# protoboard.net
KiCad netlist of a schematic drawn in Altium Designer
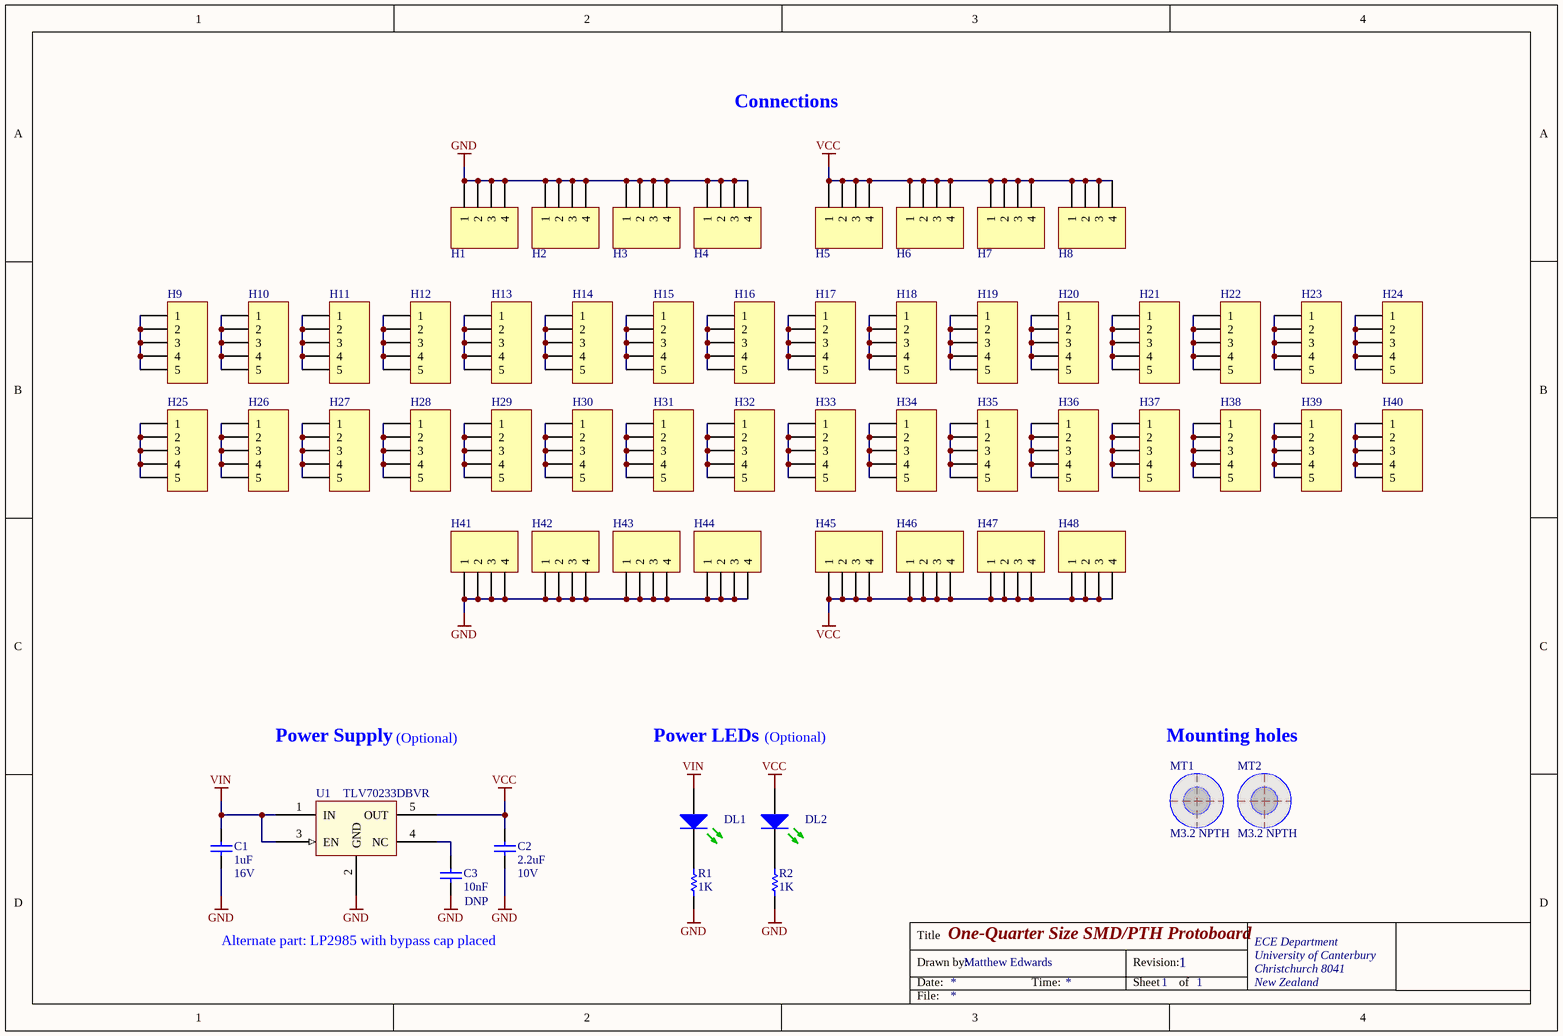
[diagram p0: protoboard.SchDoc]

(export (version "E")
  (design (tool "Eeschema 10.0.6"))
  (components
    (comp (ref "C1")
      (value "1uF")
      (footprint "CAPC1608L")
      (description "CAP CER 1uF Y5V -20% +80% 16V 0603")
      (fields (field (name "MAX VOLTAGE") "16V"))
      (libsource (lib "CAP_MLCC_E12") (part "CC_1uF_0603"))
    )
    (comp (ref "C2")
      (value "2.2uF")
      (footprint "CAPC1608L")
      (description "CAP CER 2.2uF X5R +-20% 10V 0603")
      (fields (field (name "MAX VOLTAGE") "10V"))
      (libsource (lib "CAP_MLCC_E12") (part "CC_2.2uF_0603"))
    )
    (comp (ref "C3")
      (value "DNP")
      (footprint "CAPC1608L")
      (description "CAP CER 10nF X7R +-10% 50V 0603")
      (fields (field (name "ALTIUM_VALUE") "10nF"))
      (libsource (lib "CAP_MLCC_E12") (part "CC_10nF_0603"))
    )
    (comp (ref "DL1")
      (value "Dark Green")
      (footprint "WL-SMCW0603")
      (description "LED Dk Green 430mcd 0603 SMD")
      (fields
        (field (name "MANUFACTURER") "WURTH ELEKTRONIK")
        (field (name "MANUFACTURER PART NUMBER") "150060GS75000")
      )
      (libsource (lib "SEMI_DISCRETE") (part "DL_150060GS75000"))
    )
    (comp (ref "DL2")
      (value "Dark Green")
      (footprint "WL-SMCW0603")
      (description "LED Dk Green 430mcd 0603 SMD")
      (fields
        (field (name "MANUFACTURER") "WURTH ELEKTRONIK")
        (field (name "MANUFACTURER PART NUMBER") "150060GS75000")
      )
      (libsource (lib "SEMI_DISCRETE") (part "DL_150060GS75000"))
    )
    (comp (ref "H1")
      (value "CONN_04")
      (footprint "1X04 hex")
      (description "CONN HEADER 4POS 2.54mm VERT_Thru Hole")
      (libsource (lib "protoboard") (part "CONN_04"))
    )
    (comp (ref "H2")
      (value "CONN_04")
      (footprint "1X04 hex")
      (description "CONN HEADER 4POS 2.54mm VERT_Thru Hole")
      (libsource (lib "protoboard") (part "CONN_04"))
    )
    (comp (ref "H3")
      (value "CONN_04")
      (footprint "1X04 hex")
      (description "CONN HEADER 4POS 2.54mm VERT_Thru Hole")
      (libsource (lib "protoboard") (part "CONN_04"))
    )
    (comp (ref "H4")
      (value "CONN_04")
      (footprint "1X04 hex")
      (description "CONN HEADER 4POS 2.54mm VERT_Thru Hole")
      (libsource (lib "protoboard") (part "CONN_04"))
    )
    (comp (ref "H5")
      (value "CONN_04")
      (footprint "1X04 hex")
      (description "CONN HEADER 4POS 2.54mm VERT_Thru Hole")
      (libsource (lib "protoboard") (part "CONN_04"))
    )
    (comp (ref "H6")
      (value "CONN_04")
      (footprint "1X04 hex")
      (description "CONN HEADER 4POS 2.54mm VERT_Thru Hole")
      (libsource (lib "protoboard") (part "CONN_04"))
    )
    (comp (ref "H7")
      (value "CONN_04")
      (footprint "1X04 hex")
      (description "CONN HEADER 4POS 2.54mm VERT_Thru Hole")
      (libsource (lib "protoboard") (part "CONN_04"))
    )
    (comp (ref "H8")
      (value "CONN_04")
      (footprint "1X04 hex")
      (description "CONN HEADER 4POS 2.54mm VERT_Thru Hole")
      (libsource (lib "protoboard") (part "CONN_04"))
    )
    (comp (ref "H9")
      (value "CONN_05")
      (footprint "1X05 square")
      (description "CONN HEADER 5POS 2.54mm VERT_Thru Hole")
      (libsource (lib "protoboard") (part "CONN_05"))
    )
    (comp (ref "H10")
      (value "CONN_05")
      (footprint "1X05 square")
      (description "CONN HEADER 5POS 2.54mm VERT_Thru Hole")
      (libsource (lib "protoboard") (part "CONN_05"))
    )
    (comp (ref "H11")
      (value "CONN_05")
      (footprint "1X05 square")
      (description "CONN HEADER 5POS 2.54mm VERT_Thru Hole")
      (libsource (lib "protoboard") (part "CONN_05"))
    )
    (comp (ref "H12")
      (value "CONN_05")
      (footprint "1X05 square")
      (description "CONN HEADER 5POS 2.54mm VERT_Thru Hole")
      (libsource (lib "protoboard") (part "CONN_05"))
    )
    (comp (ref "H13")
      (value "CONN_05")
      (footprint "1X05 square")
      (description "CONN HEADER 5POS 2.54mm VERT_Thru Hole")
      (libsource (lib "protoboard") (part "CONN_05"))
    )
    (comp (ref "H14")
      (value "CONN_05")
      (footprint "1X05 square")
      (description "CONN HEADER 5POS 2.54mm VERT_Thru Hole")
      (libsource (lib "protoboard") (part "CONN_05"))
    )
    (comp (ref "H15")
      (value "CONN_05")
      (footprint "1X05 square")
      (description "CONN HEADER 5POS 2.54mm VERT_Thru Hole")
      (libsource (lib "protoboard") (part "CONN_05"))
    )
    (comp (ref "H16")
      (value "CONN_05")
      (footprint "1X05 square")
      (description "CONN HEADER 5POS 2.54mm VERT_Thru Hole")
      (libsource (lib "protoboard") (part "CONN_05"))
    )
    (comp (ref "H17")
      (value "CONN_05")
      (footprint "1X05 square")
      (description "CONN HEADER 5POS 2.54mm VERT_Thru Hole")
      (libsource (lib "protoboard") (part "CONN_05"))
    )
    (comp (ref "H18")
      (value "CONN_05")
      (footprint "1X05 square")
      (description "CONN HEADER 5POS 2.54mm VERT_Thru Hole")
      (libsource (lib "protoboard") (part "CONN_05"))
    )
    (comp (ref "H19")
      (value "CONN_05")
      (footprint "1X05 square")
      (description "CONN HEADER 5POS 2.54mm VERT_Thru Hole")
      (libsource (lib "protoboard") (part "CONN_05"))
    )
    (comp (ref "H20")
      (value "CONN_05")
      (footprint "1X05 square")
      (description "CONN HEADER 5POS 2.54mm VERT_Thru Hole")
      (libsource (lib "protoboard") (part "CONN_05"))
    )
    (comp (ref "H21")
      (value "CONN_05")
      (footprint "1X05 square")
      (description "CONN HEADER 5POS 2.54mm VERT_Thru Hole")
      (libsource (lib "protoboard") (part "CONN_05"))
    )
    (comp (ref "H22")
      (value "CONN_05")
      (footprint "1X05 square")
      (description "CONN HEADER 5POS 2.54mm VERT_Thru Hole")
      (libsource (lib "protoboard") (part "CONN_05"))
    )
    (comp (ref "H23")
      (value "CONN_05")
      (footprint "1X05 square")
      (description "CONN HEADER 5POS 2.54mm VERT_Thru Hole")
      (libsource (lib "protoboard") (part "CONN_05"))
    )
    (comp (ref "H24")
      (value "CONN_05")
      (footprint "1X05 square")
      (description "CONN HEADER 5POS 2.54mm VERT_Thru Hole")
      (libsource (lib "protoboard") (part "CONN_05"))
    )
    (comp (ref "H25")
      (value "CONN_05")
      (footprint "1X05 square")
      (description "CONN HEADER 5POS 2.54mm VERT_Thru Hole")
      (libsource (lib "protoboard") (part "CONN_05"))
    )
    (comp (ref "H26")
      (value "CONN_05")
      (footprint "1X05 square")
      (description "CONN HEADER 5POS 2.54mm VERT_Thru Hole")
      (libsource (lib "protoboard") (part "CONN_05"))
    )
    (comp (ref "H27")
      (value "CONN_05")
      (footprint "1X05 square")
      (description "CONN HEADER 5POS 2.54mm VERT_Thru Hole")
      (libsource (lib "protoboard") (part "CONN_05"))
    )
    (comp (ref "H28")
      (value "CONN_05")
      (footprint "1X05 square")
      (description "CONN HEADER 5POS 2.54mm VERT_Thru Hole")
      (libsource (lib "protoboard") (part "CONN_05"))
    )
    (comp (ref "H29")
      (value "CONN_05")
      (footprint "1X05 square")
      (description "CONN HEADER 5POS 2.54mm VERT_Thru Hole")
      (libsource (lib "protoboard") (part "CONN_05"))
    )
    (comp (ref "H30")
      (value "CONN_05")
      (footprint "1X05 square")
      (description "CONN HEADER 5POS 2.54mm VERT_Thru Hole")
      (libsource (lib "protoboard") (part "CONN_05"))
    )
    (comp (ref "H31")
      (value "CONN_05")
      (footprint "1X05 square")
      (description "CONN HEADER 5POS 2.54mm VERT_Thru Hole")
      (libsource (lib "protoboard") (part "CONN_05"))
    )
    (comp (ref "H32")
      (value "CONN_05")
      (footprint "1X05 square")
      (description "CONN HEADER 5POS 2.54mm VERT_Thru Hole")
      (libsource (lib "protoboard") (part "CONN_05"))
    )
    (comp (ref "H33")
      (value "CONN_05")
      (footprint "1X05 square")
      (description "CONN HEADER 5POS 2.54mm VERT_Thru Hole")
      (libsource (lib "protoboard") (part "CONN_05"))
    )
    (comp (ref "H34")
      (value "CONN_05")
      (footprint "1X05 square")
      (description "CONN HEADER 5POS 2.54mm VERT_Thru Hole")
      (libsource (lib "protoboard") (part "CONN_05"))
    )
    (comp (ref "H35")
      (value "CONN_05")
      (footprint "1X05 square")
      (description "CONN HEADER 5POS 2.54mm VERT_Thru Hole")
      (libsource (lib "protoboard") (part "CONN_05"))
    )
    (comp (ref "H36")
      (value "CONN_05")
      (footprint "1X05 square")
      (description "CONN HEADER 5POS 2.54mm VERT_Thru Hole")
      (libsource (lib "protoboard") (part "CONN_05"))
    )
    (comp (ref "H37")
      (value "CONN_05")
      (footprint "1X05 square")
      (description "CONN HEADER 5POS 2.54mm VERT_Thru Hole")
      (libsource (lib "protoboard") (part "CONN_05"))
    )
    (comp (ref "H38")
      (value "CONN_05")
      (footprint "1X05 square")
      (description "CONN HEADER 5POS 2.54mm VERT_Thru Hole")
      (libsource (lib "protoboard") (part "CONN_05"))
    )
    (comp (ref "H39")
      (value "CONN_05")
      (footprint "1X05 square")
      (description "CONN HEADER 5POS 2.54mm VERT_Thru Hole")
      (libsource (lib "protoboard") (part "CONN_05"))
    )
    (comp (ref "H40")
      (value "CONN_05")
      (footprint "1X05 square")
      (description "CONN HEADER 5POS 2.54mm VERT_Thru Hole")
      (libsource (lib "protoboard") (part "CONN_05"))
    )
    (comp (ref "H41")
      (value "CONN_04")
      (footprint "1X04 hex")
      (description "CONN HEADER 4POS 2.54mm VERT_Thru Hole")
      (libsource (lib "") (part "CONN_04_1"))
    )
    (comp (ref "H42")
      (value "CONN_04")
      (footprint "1X04 hex")
      (description "CONN HEADER 4POS 2.54mm VERT_Thru Hole")
      (libsource (lib "") (part "CONN_04_1"))
    )
    (comp (ref "H43")
      (value "CONN_04")
      (footprint "1X04 hex")
      (description "CONN HEADER 4POS 2.54mm VERT_Thru Hole")
      (libsource (lib "") (part "CONN_04_1"))
    )
    (comp (ref "H44")
      (value "CONN_04")
      (footprint "1X04 hex")
      (description "CONN HEADER 4POS 2.54mm VERT_Thru Hole")
      (libsource (lib "") (part "CONN_04_1"))
    )
    (comp (ref "H45")
      (value "CONN_04")
      (footprint "1X04 hex")
      (description "CONN HEADER 4POS 2.54mm VERT_Thru Hole")
      (libsource (lib "") (part "CONN_04_1"))
    )
    (comp (ref "H46")
      (value "CONN_04")
      (footprint "1X04 hex")
      (description "CONN HEADER 4POS 2.54mm VERT_Thru Hole")
      (libsource (lib "") (part "CONN_04_1"))
    )
    (comp (ref "H47")
      (value "CONN_04")
      (footprint "1X04 hex")
      (description "CONN HEADER 4POS 2.54mm VERT_Thru Hole")
      (libsource (lib "") (part "CONN_04_1"))
    )
    (comp (ref "H48")
      (value "CONN_04")
      (footprint "1X04 hex")
      (description "CONN HEADER 4POS 2.54mm VERT_Thru Hole")
      (libsource (lib "") (part "CONN_04_1"))
    )
    (comp (ref "MT1")
      (value "M3.2 NPTH")
      (footprint "MNT-HOLE_3.2mm_NPTH")
      (description "Fixing M3.2 Mount Hole NPTH")
      (fields (field (name "MANUFACTURER") "Hi-Q"))
      (libsource (lib "MISC_Passive") (part "MC_M3.2_HOLE"))
    )
    (comp (ref "MT2")
      (value "M3.2 NPTH")
      (footprint "MNT-HOLE_3.2mm_NPTH")
      (description "Fixing M3.2 Mount Hole NPTH")
      (fields (field (name "MANUFACTURER") "Hi-Q"))
      (libsource (lib "MISC_Passive") (part "MC_M3.2_HOLE"))
    )
    (comp (ref "R1")
      (value "1K")
      (footprint "RESC1608L")
      (description "RES 1.0K OHM 1/10W 5% 0603 SMD")
      (libsource (lib "RES_0603_0.1W_E24") (part "RS_1K"))
    )
    (comp (ref "R2")
      (value "1K")
      (footprint "RESC1608L")
      (description "RES 1.0K OHM 1/10W 5% 0603 SMD")
      (libsource (lib "RES_0603_0.1W_E24") (part "RS_1K"))
    )
    (comp (ref "U1")
      (value "TLV70233DBVR")
      (footprint "SOT95P280X145-5N")
      (description "IC REG LDO 3.3V 0.3A SOT23-5")
      (fields
        (field (name "MANUFACTURER") "Texas Instruments")
        (field (name "MANUFACTURER PART NUMBER") "TLV70233DBVR")
      )
      (libsource (lib "SEMI_DISCRETE") (part "SV_TLV70233DBVR"))
    )
  )
  (nets
    (net (code "1") (name "GND") (class "Default")
      (node (ref "C1") (pin "1") (pinfunction "1_1") (pintype "passive"))
      (node (ref "C2") (pin "1") (pinfunction "1_1") (pintype "passive"))
      (node (ref "C3") (pin "2") (pinfunction "2_2") (pintype "passive"))
      (node (ref "H1") (pin "1") (pinfunction "1_1") (pintype "passive"))
      (node (ref "H1") (pin "2") (pinfunction "2_2") (pintype "passive"))
      (node (ref "H1") (pin "3") (pinfunction "3_3") (pintype "passive"))
      (node (ref "H1") (pin "4") (pinfunction "4_4") (pintype "passive"))
      (node (ref "H2") (pin "1") (pinfunction "1_1") (pintype "passive"))
      (node (ref "H2") (pin "2") (pinfunction "2_2") (pintype "passive"))
      (node (ref "H2") (pin "3") (pinfunction "3_3") (pintype "passive"))
      (node (ref "H2") (pin "4") (pinfunction "4_4") (pintype "passive"))
      (node (ref "H3") (pin "1") (pinfunction "1_1") (pintype "passive"))
      (node (ref "H3") (pin "2") (pinfunction "2_2") (pintype "passive"))
      (node (ref "H3") (pin "3") (pinfunction "3_3") (pintype "passive"))
      (node (ref "H3") (pin "4") (pinfunction "4_4") (pintype "passive"))
      (node (ref "H4") (pin "1") (pinfunction "1_1") (pintype "passive"))
      (node (ref "H4") (pin "2") (pinfunction "2_2") (pintype "passive"))
      (node (ref "H4") (pin "3") (pinfunction "3_3") (pintype "passive"))
      (node (ref "H4") (pin "4") (pinfunction "4_4") (pintype "passive"))
      (node (ref "H41") (pin "1") (pinfunction "1_1") (pintype "passive"))
      (node (ref "H41") (pin "2") (pinfunction "2_2") (pintype "passive"))
      (node (ref "H41") (pin "3") (pinfunction "3_3") (pintype "passive"))
      (node (ref "H41") (pin "4") (pinfunction "4_4") (pintype "passive"))
      (node (ref "H42") (pin "1") (pinfunction "1_1") (pintype "passive"))
      (node (ref "H42") (pin "2") (pinfunction "2_2") (pintype "passive"))
      (node (ref "H42") (pin "3") (pinfunction "3_3") (pintype "passive"))
      (node (ref "H42") (pin "4") (pinfunction "4_4") (pintype "passive"))
      (node (ref "H43") (pin "1") (pinfunction "1_1") (pintype "passive"))
      (node (ref "H43") (pin "2") (pinfunction "2_2") (pintype "passive"))
      (node (ref "H43") (pin "3") (pinfunction "3_3") (pintype "passive"))
      (node (ref "H43") (pin "4") (pinfunction "4_4") (pintype "passive"))
      (node (ref "H44") (pin "1") (pinfunction "1_1") (pintype "passive"))
      (node (ref "H44") (pin "2") (pinfunction "2_2") (pintype "passive"))
      (node (ref "H44") (pin "3") (pinfunction "3_3") (pintype "passive"))
      (node (ref "H44") (pin "4") (pinfunction "4_4") (pintype "passive"))
      (node (ref "R1") (pin "1") (pinfunction "1_1") (pintype "passive"))
      (node (ref "R2") (pin "1") (pinfunction "1_1") (pintype "passive"))
      (node (ref "U1") (pin "2") (pinfunction "GND_2") (pintype "power_in"))
    )
    (net (code "2") (name "Net-(DL1-K)") (class "Default")
      (node (ref "DL1") (pin "1") (pinfunction "K_1") (pintype "passive"))
      (node (ref "R1") (pin "2") (pinfunction "2_2") (pintype "passive"))
    )
    (net (code "3") (name "Net-(DL2-K)") (class "Default")
      (node (ref "DL2") (pin "1") (pinfunction "K_1") (pintype "passive"))
      (node (ref "R2") (pin "2") (pinfunction "2_2") (pintype "passive"))
    )
    (net (code "4") (name "Net-(H9-Pad1)") (class "Default")
      (node (ref "H9") (pin "1") (pinfunction "1_1") (pintype "passive"))
      (node (ref "H9") (pin "2") (pinfunction "2_2") (pintype "passive"))
      (node (ref "H9") (pin "3") (pinfunction "3_3") (pintype "passive"))
      (node (ref "H9") (pin "4") (pinfunction "4_4") (pintype "passive"))
      (node (ref "H9") (pin "5") (pinfunction "5_5") (pintype "passive"))
    )
    (net (code "5") (name "Net-(H10-Pad1)") (class "Default")
      (node (ref "H10") (pin "1") (pinfunction "1_1") (pintype "passive"))
      (node (ref "H10") (pin "2") (pinfunction "2_2") (pintype "passive"))
      (node (ref "H10") (pin "3") (pinfunction "3_3") (pintype "passive"))
      (node (ref "H10") (pin "4") (pinfunction "4_4") (pintype "passive"))
      (node (ref "H10") (pin "5") (pinfunction "5_5") (pintype "passive"))
    )
    (net (code "6") (name "Net-(H11-Pad1)") (class "Default")
      (node (ref "H11") (pin "1") (pinfunction "1_1") (pintype "passive"))
      (node (ref "H11") (pin "2") (pinfunction "2_2") (pintype "passive"))
      (node (ref "H11") (pin "3") (pinfunction "3_3") (pintype "passive"))
      (node (ref "H11") (pin "4") (pinfunction "4_4") (pintype "passive"))
      (node (ref "H11") (pin "5") (pinfunction "5_5") (pintype "passive"))
    )
    (net (code "7") (name "Net-(H12-Pad1)") (class "Default")
      (node (ref "H12") (pin "1") (pinfunction "1_1") (pintype "passive"))
      (node (ref "H12") (pin "2") (pinfunction "2_2") (pintype "passive"))
      (node (ref "H12") (pin "3") (pinfunction "3_3") (pintype "passive"))
      (node (ref "H12") (pin "4") (pinfunction "4_4") (pintype "passive"))
      (node (ref "H12") (pin "5") (pinfunction "5_5") (pintype "passive"))
    )
    (net (code "8") (name "Net-(H13-Pad1)") (class "Default")
      (node (ref "H13") (pin "1") (pinfunction "1_1") (pintype "passive"))
      (node (ref "H13") (pin "2") (pinfunction "2_2") (pintype "passive"))
      (node (ref "H13") (pin "3") (pinfunction "3_3") (pintype "passive"))
      (node (ref "H13") (pin "4") (pinfunction "4_4") (pintype "passive"))
      (node (ref "H13") (pin "5") (pinfunction "5_5") (pintype "passive"))
    )
    (net (code "9") (name "Net-(H14-Pad1)") (class "Default")
      (node (ref "H14") (pin "1") (pinfunction "1_1") (pintype "passive"))
      (node (ref "H14") (pin "2") (pinfunction "2_2") (pintype "passive"))
      (node (ref "H14") (pin "3") (pinfunction "3_3") (pintype "passive"))
      (node (ref "H14") (pin "4") (pinfunction "4_4") (pintype "passive"))
      (node (ref "H14") (pin "5") (pinfunction "5_5") (pintype "passive"))
    )
    (net (code "10") (name "Net-(H15-Pad1)") (class "Default")
      (node (ref "H15") (pin "1") (pinfunction "1_1") (pintype "passive"))
      (node (ref "H15") (pin "2") (pinfunction "2_2") (pintype "passive"))
      (node (ref "H15") (pin "3") (pinfunction "3_3") (pintype "passive"))
      (node (ref "H15") (pin "4") (pinfunction "4_4") (pintype "passive"))
      (node (ref "H15") (pin "5") (pinfunction "5_5") (pintype "passive"))
    )
    (net (code "11") (name "Net-(H16-Pad1)") (class "Default")
      (node (ref "H16") (pin "1") (pinfunction "1_1") (pintype "passive"))
      (node (ref "H16") (pin "2") (pinfunction "2_2") (pintype "passive"))
      (node (ref "H16") (pin "3") (pinfunction "3_3") (pintype "passive"))
      (node (ref "H16") (pin "4") (pinfunction "4_4") (pintype "passive"))
      (node (ref "H16") (pin "5") (pinfunction "5_5") (pintype "passive"))
    )
    (net (code "12") (name "Net-(H17-Pad1)") (class "Default")
      (node (ref "H17") (pin "1") (pinfunction "1_1") (pintype "passive"))
      (node (ref "H17") (pin "2") (pinfunction "2_2") (pintype "passive"))
      (node (ref "H17") (pin "3") (pinfunction "3_3") (pintype "passive"))
      (node (ref "H17") (pin "4") (pinfunction "4_4") (pintype "passive"))
      (node (ref "H17") (pin "5") (pinfunction "5_5") (pintype "passive"))
    )
    (net (code "13") (name "Net-(H18-Pad1)") (class "Default")
      (node (ref "H18") (pin "1") (pinfunction "1_1") (pintype "passive"))
      (node (ref "H18") (pin "2") (pinfunction "2_2") (pintype "passive"))
      (node (ref "H18") (pin "3") (pinfunction "3_3") (pintype "passive"))
      (node (ref "H18") (pin "4") (pinfunction "4_4") (pintype "passive"))
      (node (ref "H18") (pin "5") (pinfunction "5_5") (pintype "passive"))
    )
    (net (code "14") (name "Net-(H19-Pad1)") (class "Default")
      (node (ref "H19") (pin "1") (pinfunction "1_1") (pintype "passive"))
      (node (ref "H19") (pin "2") (pinfunction "2_2") (pintype "passive"))
      (node (ref "H19") (pin "3") (pinfunction "3_3") (pintype "passive"))
      (node (ref "H19") (pin "4") (pinfunction "4_4") (pintype "passive"))
      (node (ref "H19") (pin "5") (pinfunction "5_5") (pintype "passive"))
    )
    (net (code "15") (name "Net-(H20-Pad1)") (class "Default")
      (node (ref "H20") (pin "1") (pinfunction "1_1") (pintype "passive"))
      (node (ref "H20") (pin "2") (pinfunction "2_2") (pintype "passive"))
      (node (ref "H20") (pin "3") (pinfunction "3_3") (pintype "passive"))
      (node (ref "H20") (pin "4") (pinfunction "4_4") (pintype "passive"))
      (node (ref "H20") (pin "5") (pinfunction "5_5") (pintype "passive"))
    )
    (net (code "16") (name "Net-(H21-Pad1)") (class "Default")
      (node (ref "H21") (pin "1") (pinfunction "1_1") (pintype "passive"))
      (node (ref "H21") (pin "2") (pinfunction "2_2") (pintype "passive"))
      (node (ref "H21") (pin "3") (pinfunction "3_3") (pintype "passive"))
      (node (ref "H21") (pin "4") (pinfunction "4_4") (pintype "passive"))
      (node (ref "H21") (pin "5") (pinfunction "5_5") (pintype "passive"))
    )
    (net (code "17") (name "Net-(H22-Pad1)") (class "Default")
      (node (ref "H22") (pin "1") (pinfunction "1_1") (pintype "passive"))
      (node (ref "H22") (pin "2") (pinfunction "2_2") (pintype "passive"))
      (node (ref "H22") (pin "3") (pinfunction "3_3") (pintype "passive"))
      (node (ref "H22") (pin "4") (pinfunction "4_4") (pintype "passive"))
      (node (ref "H22") (pin "5") (pinfunction "5_5") (pintype "passive"))
    )
    (net (code "18") (name "Net-(H23-Pad1)") (class "Default")
      (node (ref "H23") (pin "1") (pinfunction "1_1") (pintype "passive"))
      (node (ref "H23") (pin "2") (pinfunction "2_2") (pintype "passive"))
      (node (ref "H23") (pin "3") (pinfunction "3_3") (pintype "passive"))
      (node (ref "H23") (pin "4") (pinfunction "4_4") (pintype "passive"))
      (node (ref "H23") (pin "5") (pinfunction "5_5") (pintype "passive"))
    )
    (net (code "19") (name "Net-(H24-Pad1)") (class "Default")
      (node (ref "H24") (pin "1") (pinfunction "1_1") (pintype "passive"))
      (node (ref "H24") (pin "2") (pinfunction "2_2") (pintype "passive"))
      (node (ref "H24") (pin "3") (pinfunction "3_3") (pintype "passive"))
      (node (ref "H24") (pin "4") (pinfunction "4_4") (pintype "passive"))
      (node (ref "H24") (pin "5") (pinfunction "5_5") (pintype "passive"))
    )
    (net (code "20") (name "Net-(H25-Pad1)") (class "Default")
      (node (ref "H25") (pin "1") (pinfunction "1_1") (pintype "passive"))
      (node (ref "H25") (pin "2") (pinfunction "2_2") (pintype "passive"))
      (node (ref "H25") (pin "3") (pinfunction "3_3") (pintype "passive"))
      (node (ref "H25") (pin "4") (pinfunction "4_4") (pintype "passive"))
      (node (ref "H25") (pin "5") (pinfunction "5_5") (pintype "passive"))
    )
    (net (code "21") (name "Net-(H26-Pad1)") (class "Default")
      (node (ref "H26") (pin "1") (pinfunction "1_1") (pintype "passive"))
      (node (ref "H26") (pin "2") (pinfunction "2_2") (pintype "passive"))
      (node (ref "H26") (pin "3") (pinfunction "3_3") (pintype "passive"))
      (node (ref "H26") (pin "4") (pinfunction "4_4") (pintype "passive"))
      (node (ref "H26") (pin "5") (pinfunction "5_5") (pintype "passive"))
    )
    (net (code "22") (name "Net-(H27-Pad1)") (class "Default")
      (node (ref "H27") (pin "1") (pinfunction "1_1") (pintype "passive"))
      (node (ref "H27") (pin "2") (pinfunction "2_2") (pintype "passive"))
      (node (ref "H27") (pin "3") (pinfunction "3_3") (pintype "passive"))
      (node (ref "H27") (pin "4") (pinfunction "4_4") (pintype "passive"))
      (node (ref "H27") (pin "5") (pinfunction "5_5") (pintype "passive"))
    )
    (net (code "23") (name "Net-(H28-Pad1)") (class "Default")
      (node (ref "H28") (pin "1") (pinfunction "1_1") (pintype "passive"))
      (node (ref "H28") (pin "2") (pinfunction "2_2") (pintype "passive"))
      (node (ref "H28") (pin "3") (pinfunction "3_3") (pintype "passive"))
      (node (ref "H28") (pin "4") (pinfunction "4_4") (pintype "passive"))
      (node (ref "H28") (pin "5") (pinfunction "5_5") (pintype "passive"))
    )
    (net (code "24") (name "Net-(H29-Pad1)") (class "Default")
      (node (ref "H29") (pin "1") (pinfunction "1_1") (pintype "passive"))
      (node (ref "H29") (pin "2") (pinfunction "2_2") (pintype "passive"))
      (node (ref "H29") (pin "3") (pinfunction "3_3") (pintype "passive"))
      (node (ref "H29") (pin "4") (pinfunction "4_4") (pintype "passive"))
      (node (ref "H29") (pin "5") (pinfunction "5_5") (pintype "passive"))
    )
    (net (code "25") (name "Net-(H30-Pad1)") (class "Default")
      (node (ref "H30") (pin "1") (pinfunction "1_1") (pintype "passive"))
      (node (ref "H30") (pin "2") (pinfunction "2_2") (pintype "passive"))
      (node (ref "H30") (pin "3") (pinfunction "3_3") (pintype "passive"))
      (node (ref "H30") (pin "4") (pinfunction "4_4") (pintype "passive"))
      (node (ref "H30") (pin "5") (pinfunction "5_5") (pintype "passive"))
    )
    (net (code "26") (name "Net-(H31-Pad1)") (class "Default")
      (node (ref "H31") (pin "1") (pinfunction "1_1") (pintype "passive"))
      (node (ref "H31") (pin "2") (pinfunction "2_2") (pintype "passive"))
      (node (ref "H31") (pin "3") (pinfunction "3_3") (pintype "passive"))
      (node (ref "H31") (pin "4") (pinfunction "4_4") (pintype "passive"))
      (node (ref "H31") (pin "5") (pinfunction "5_5") (pintype "passive"))
    )
    (net (code "27") (name "Net-(H32-Pad1)") (class "Default")
      (node (ref "H32") (pin "1") (pinfunction "1_1") (pintype "passive"))
      (node (ref "H32") (pin "2") (pinfunction "2_2") (pintype "passive"))
      (node (ref "H32") (pin "3") (pinfunction "3_3") (pintype "passive"))
      (node (ref "H32") (pin "4") (pinfunction "4_4") (pintype "passive"))
      (node (ref "H32") (pin "5") (pinfunction "5_5") (pintype "passive"))
    )
    (net (code "28") (name "Net-(H33-Pad1)") (class "Default")
      (node (ref "H33") (pin "1") (pinfunction "1_1") (pintype "passive"))
      (node (ref "H33") (pin "2") (pinfunction "2_2") (pintype "passive"))
      (node (ref "H33") (pin "3") (pinfunction "3_3") (pintype "passive"))
      (node (ref "H33") (pin "4") (pinfunction "4_4") (pintype "passive"))
      (node (ref "H33") (pin "5") (pinfunction "5_5") (pintype "passive"))
    )
    (net (code "29") (name "Net-(H34-Pad1)") (class "Default")
      (node (ref "H34") (pin "1") (pinfunction "1_1") (pintype "passive"))
      (node (ref "H34") (pin "2") (pinfunction "2_2") (pintype "passive"))
      (node (ref "H34") (pin "3") (pinfunction "3_3") (pintype "passive"))
      (node (ref "H34") (pin "4") (pinfunction "4_4") (pintype "passive"))
      (node (ref "H34") (pin "5") (pinfunction "5_5") (pintype "passive"))
    )
    (net (code "30") (name "Net-(H35-Pad1)") (class "Default")
      (node (ref "H35") (pin "1") (pinfunction "1_1") (pintype "passive"))
      (node (ref "H35") (pin "2") (pinfunction "2_2") (pintype "passive"))
      (node (ref "H35") (pin "3") (pinfunction "3_3") (pintype "passive"))
      (node (ref "H35") (pin "4") (pinfunction "4_4") (pintype "passive"))
      (node (ref "H35") (pin "5") (pinfunction "5_5") (pintype "passive"))
    )
    (net (code "31") (name "Net-(H36-Pad1)") (class "Default")
      (node (ref "H36") (pin "1") (pinfunction "1_1") (pintype "passive"))
      (node (ref "H36") (pin "2") (pinfunction "2_2") (pintype "passive"))
      (node (ref "H36") (pin "3") (pinfunction "3_3") (pintype "passive"))
      (node (ref "H36") (pin "4") (pinfunction "4_4") (pintype "passive"))
      (node (ref "H36") (pin "5") (pinfunction "5_5") (pintype "passive"))
    )
    (net (code "32") (name "Net-(H37-Pad1)") (class "Default")
      (node (ref "H37") (pin "1") (pinfunction "1_1") (pintype "passive"))
      (node (ref "H37") (pin "2") (pinfunction "2_2") (pintype "passive"))
      (node (ref "H37") (pin "3") (pinfunction "3_3") (pintype "passive"))
      (node (ref "H37") (pin "4") (pinfunction "4_4") (pintype "passive"))
      (node (ref "H37") (pin "5") (pinfunction "5_5") (pintype "passive"))
    )
    (net (code "33") (name "Net-(H38-Pad1)") (class "Default")
      (node (ref "H38") (pin "1") (pinfunction "1_1") (pintype "passive"))
      (node (ref "H38") (pin "2") (pinfunction "2_2") (pintype "passive"))
      (node (ref "H38") (pin "3") (pinfunction "3_3") (pintype "passive"))
      (node (ref "H38") (pin "4") (pinfunction "4_4") (pintype "passive"))
      (node (ref "H38") (pin "5") (pinfunction "5_5") (pintype "passive"))
    )
    (net (code "34") (name "Net-(H39-Pad1)") (class "Default")
      (node (ref "H39") (pin "1") (pinfunction "1_1") (pintype "passive"))
      (node (ref "H39") (pin "2") (pinfunction "2_2") (pintype "passive"))
      (node (ref "H39") (pin "3") (pinfunction "3_3") (pintype "passive"))
      (node (ref "H39") (pin "4") (pinfunction "4_4") (pintype "passive"))
      (node (ref "H39") (pin "5") (pinfunction "5_5") (pintype "passive"))
    )
    (net (code "35") (name "Net-(H40-Pad1)") (class "Default")
      (node (ref "H40") (pin "1") (pinfunction "1_1") (pintype "passive"))
      (node (ref "H40") (pin "2") (pinfunction "2_2") (pintype "passive"))
      (node (ref "H40") (pin "3") (pinfunction "3_3") (pintype "passive"))
      (node (ref "H40") (pin "4") (pinfunction "4_4") (pintype "passive"))
      (node (ref "H40") (pin "5") (pinfunction "5_5") (pintype "passive"))
    )
    (net (code "36") (name "Net-(U1-NC)") (class "Default")
      (node (ref "C3") (pin "1") (pinfunction "1_1") (pintype "passive"))
      (node (ref "U1") (pin "4") (pinfunction "NC_4") (pintype "passive"))
    )
    (net (code "37") (name "VCC") (class "Default")
      (node (ref "C2") (pin "2") (pinfunction "2_2") (pintype "passive"))
      (node (ref "DL2") (pin "2") (pinfunction "A_2") (pintype "passive"))
      (node (ref "H45") (pin "1") (pinfunction "1_1") (pintype "passive"))
      (node (ref "H45") (pin "2") (pinfunction "2_2") (pintype "passive"))
      (node (ref "H45") (pin "3") (pinfunction "3_3") (pintype "passive"))
      (node (ref "H45") (pin "4") (pinfunction "4_4") (pintype "passive"))
      (node (ref "H46") (pin "1") (pinfunction "1_1") (pintype "passive"))
      (node (ref "H46") (pin "2") (pinfunction "2_2") (pintype "passive"))
      (node (ref "H46") (pin "3") (pinfunction "3_3") (pintype "passive"))
      (node (ref "H46") (pin "4") (pinfunction "4_4") (pintype "passive"))
      (node (ref "H47") (pin "1") (pinfunction "1_1") (pintype "passive"))
      (node (ref "H47") (pin "2") (pinfunction "2_2") (pintype "passive"))
      (node (ref "H47") (pin "3") (pinfunction "3_3") (pintype "passive"))
      (node (ref "H47") (pin "4") (pinfunction "4_4") (pintype "passive"))
      (node (ref "H48") (pin "1") (pinfunction "1_1") (pintype "passive"))
      (node (ref "H48") (pin "2") (pinfunction "2_2") (pintype "passive"))
      (node (ref "H48") (pin "3") (pinfunction "3_3") (pintype "passive"))
      (node (ref "H48") (pin "4") (pinfunction "4_4") (pintype "passive"))
      (node (ref "H5") (pin "1") (pinfunction "1_1") (pintype "passive"))
      (node (ref "H5") (pin "2") (pinfunction "2_2") (pintype "passive"))
      (node (ref "H5") (pin "3") (pinfunction "3_3") (pintype "passive"))
      (node (ref "H5") (pin "4") (pinfunction "4_4") (pintype "passive"))
      (node (ref "H6") (pin "1") (pinfunction "1_1") (pintype "passive"))
      (node (ref "H6") (pin "2") (pinfunction "2_2") (pintype "passive"))
      (node (ref "H6") (pin "3") (pinfunction "3_3") (pintype "passive"))
      (node (ref "H6") (pin "4") (pinfunction "4_4") (pintype "passive"))
      (node (ref "H7") (pin "1") (pinfunction "1_1") (pintype "passive"))
      (node (ref "H7") (pin "2") (pinfunction "2_2") (pintype "passive"))
      (node (ref "H7") (pin "3") (pinfunction "3_3") (pintype "passive"))
      (node (ref "H7") (pin "4") (pinfunction "4_4") (pintype "passive"))
      (node (ref "H8") (pin "1") (pinfunction "1_1") (pintype "passive"))
      (node (ref "H8") (pin "2") (pinfunction "2_2") (pintype "passive"))
      (node (ref "H8") (pin "3") (pinfunction "3_3") (pintype "passive"))
      (node (ref "H8") (pin "4") (pinfunction "4_4") (pintype "passive"))
      (node (ref "U1") (pin "5") (pinfunction "OUT_5") (pintype "power_in"))
    )
    (net (code "38") (name "VIN") (class "Default")
      (node (ref "C1") (pin "2") (pinfunction "2_2") (pintype "passive"))
      (node (ref "DL1") (pin "2") (pinfunction "A_2") (pintype "passive"))
      (node (ref "U1") (pin "1") (pinfunction "IN_1") (pintype "power_in"))
      (node (ref "U1") (pin "3") (pinfunction "EN_3") (pintype "input"))
    )
  )
)
